# SCH_Syntheseproject_Proof_of_concept_mot.net
KiCad netlist of a schematic drawn in EasyEDA
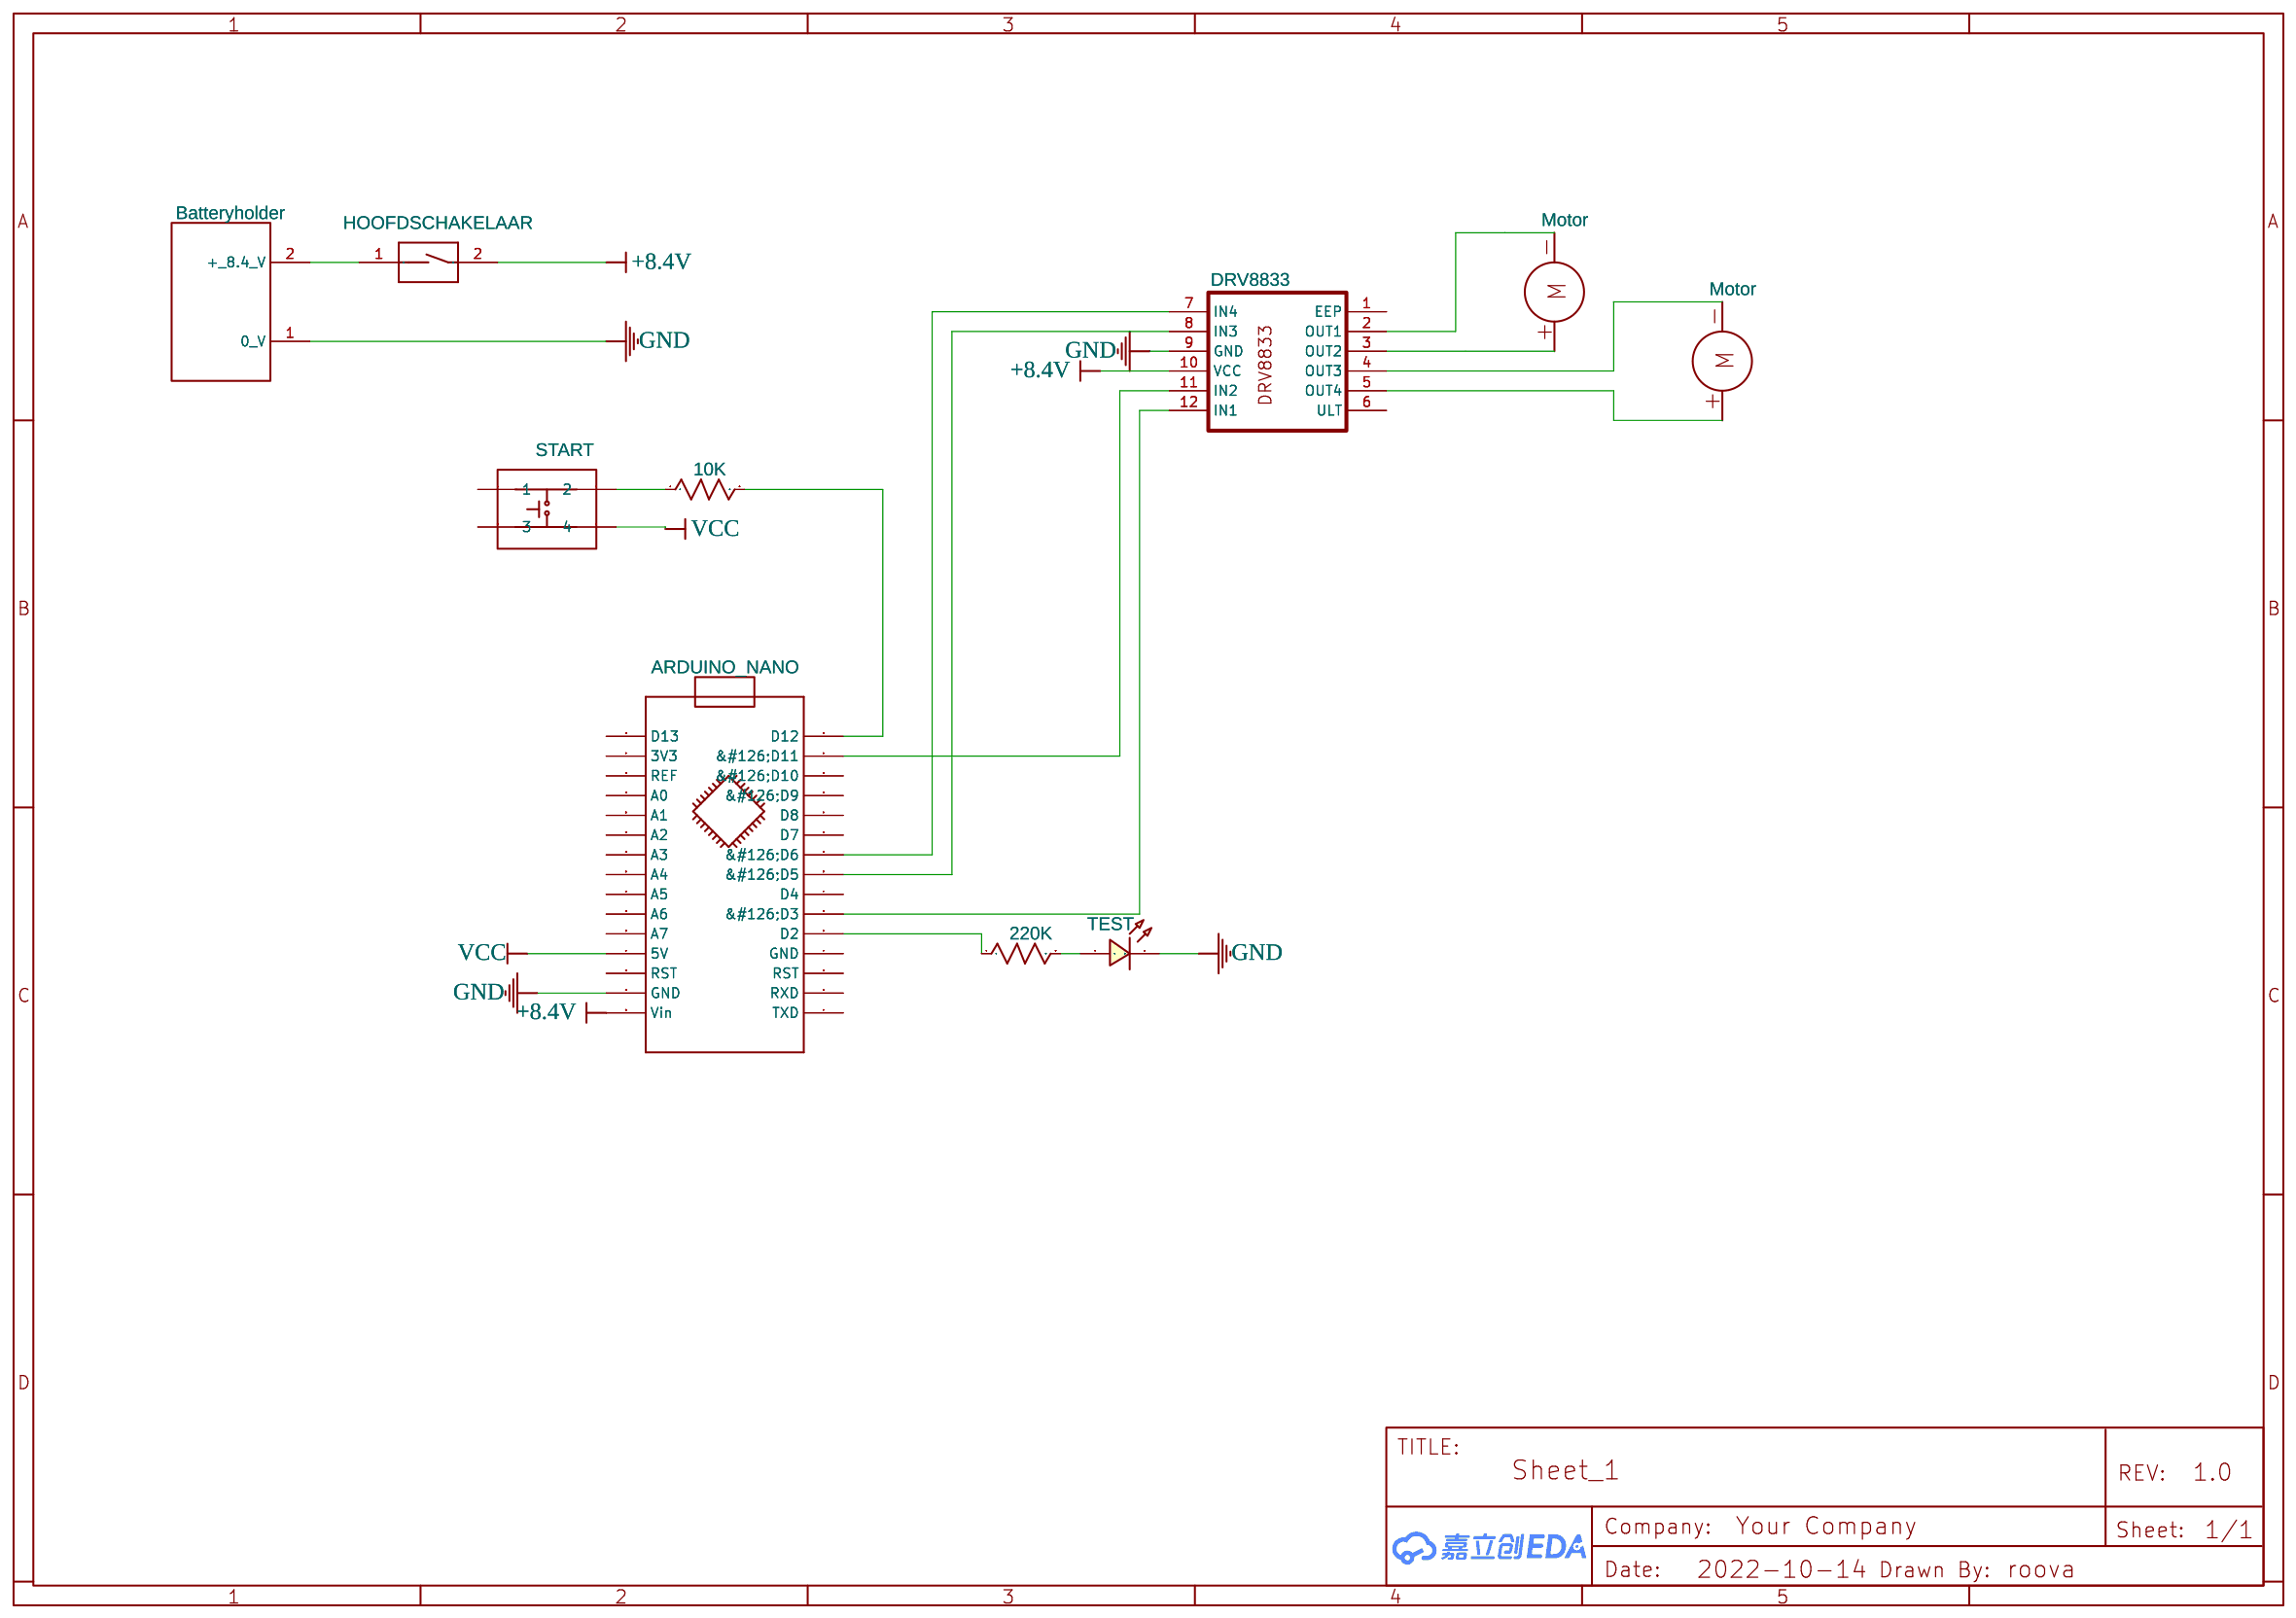
[diagram p0: schematic sheet]

(export (version "E")
  (design (tool "Eeschema 10.0.6"))
  (components
    (comp (ref "10K") (value "1k") (libsource (lib "") (part "R_0603_US_1")))
    (comp (ref "220K") (value "1k") (libsource (lib "") (part "R_0603_US")))
    (comp (ref "ARDUINO_NANO")
      (value "ARDUINO-NANO_V3")
      (fields (field (name "BOM_Manufacturer Part") "ARDUINO-NANO_AK"))
      (libsource (lib "") (part "ARDUINO-NANO_V3"))
    )
    (comp (ref "HOOFDSCHAKELAAR")
      (value "DIP1")
      (fields
        (field (name "BOM_Manufacturer Part") "A6TN-1101")
        (field (name "BOM_Supplier Part") "Z12167-ND")
      )
      (libsource (lib "") (part "DIP1"))
    )
    (comp (ref "M2") (value "Motor") (libsource (lib "") (part "Motor")))
    (comp (ref "M3") (value "Motor") (libsource (lib "") (part "Motor")))
    (comp (ref "START")
      (value "PUSHBUTTON 6X6X4.5 4 PINS COPY")
      (fields (field (name "BOM_Manufacturer Part") "sparkfun"))
      (libsource (lib "") (part "PUSHBUTTON 6X6X4.5 4 PINS COPY"))
    )
    (comp (ref "TEST")
      (value "LED-0603_R")
      (fields
        (field (name "BOM_Manufacturer Part") "19-217/R6C-AL1M2VY/3T")
        (field (name "BOM_Supplier Part") "C72044")
      )
      (libsource (lib "") (part "LED-0603_R"))
    )
    (comp (ref "U1") (value "DRV8833") (libsource (lib "") (part "DRV8833 (NO ORIGINAL)")))
    (comp (ref "U4") (value "Batteryholder") (libsource (lib "") (part "Batteryholder")))
  )
  (nets
    (net (code "1") (name "+8.4V") (class "Default")
      (node (ref "ARDUINO_NANO") (pin "30") (pinfunction "Vin_30") (pintype "unspecified"))
      (node (ref "HOOFDSCHAKELAAR") (pin "2") (pinfunction "2_2") (pintype "unspecified"))
      (node (ref "U1") (pin "10") (pinfunction "VCC_10") (pintype "unspecified"))
    )
    (net (code "2") (name "GND") (class "Default")
      (node (ref "ARDUINO_NANO") (pin "29") (pinfunction "GND_29") (pintype "unspecified"))
      (node (ref "TEST") (pin "2") (pinfunction "2_2") (pintype "unspecified"))
      (node (ref "U1") (pin "9") (pinfunction "GND_9") (pintype "unspecified"))
      (node (ref "U4") (pin "1") (pinfunction "0_V_1") (pintype "unspecified"))
    )
    (net (code "3") (name "Net-(10K-Pad1)") (class "Default")
      (node (ref "10K") (pin "1") (pinfunction "1_1") (pintype "unspecified"))
      (node (ref "START") (pin "2") (pinfunction "2_2") (pintype "unspecified"))
    )
    (net (code "4") (name "Net-(220K-Pad2)") (class "Default")
      (node (ref "220K") (pin "2") (pinfunction "2_2") (pintype "unspecified"))
      (node (ref "TEST") (pin "1") (pinfunction "1_1") (pintype "unspecified"))
    )
    (net (code "5") (name "Net-(ARDUINO_NANO-&#126;D3)") (class "Default")
      (node (ref "ARDUINO_NANO") (pin "6") (pinfunction "&#126;D3_6") (pintype "unspecified"))
      (node (ref "U1") (pin "12") (pinfunction "IN1_12") (pintype "unspecified"))
    )
    (net (code "6") (name "Net-(ARDUINO_NANO-&#126;D5)") (class "Default")
      (node (ref "ARDUINO_NANO") (pin "8") (pinfunction "&#126;D5_8") (pintype "unspecified"))
      (node (ref "U1") (pin "8") (pinfunction "IN3_8") (pintype "unspecified"))
    )
    (net (code "7") (name "Net-(ARDUINO_NANO-&#126;D6)") (class "Default")
      (node (ref "ARDUINO_NANO") (pin "9") (pinfunction "&#126;D6_9") (pintype "unspecified"))
      (node (ref "U1") (pin "7") (pinfunction "IN4_7") (pintype "unspecified"))
    )
    (net (code "8") (name "Net-(ARDUINO_NANO-&#126;D11)") (class "Default")
      (node (ref "ARDUINO_NANO") (pin "14") (pinfunction "&#126;D11_14") (pintype "unspecified"))
      (node (ref "U1") (pin "11") (pinfunction "IN2_11") (pintype "unspecified"))
    )
    (net (code "9") (name "Net-(ARDUINO_NANO-D2)") (class "Default")
      (node (ref "220K") (pin "1") (pinfunction "1_1") (pintype "unspecified"))
      (node (ref "ARDUINO_NANO") (pin "5") (pinfunction "D2_5") (pintype "unspecified"))
    )
    (net (code "10") (name "Net-(ARDUINO_NANO-D12)") (class "Default")
      (node (ref "10K") (pin "2") (pinfunction "2_2") (pintype "unspecified"))
      (node (ref "ARDUINO_NANO") (pin "15") (pinfunction "D12_15") (pintype "unspecified"))
    )
    (net (code "11") (name "Net-(U4-+_8.4_V)") (class "Default")
      (node (ref "HOOFDSCHAKELAAR") (pin "1") (pinfunction "1_1") (pintype "unspecified"))
      (node (ref "U4") (pin "2") (pinfunction "+_8.4_V_2") (pintype "unspecified"))
    )
    (net (code "12") (name "VCC") (class "Default")
      (node (ref "ARDUINO_NANO") (pin "27") (pinfunction "5V_27") (pintype "unspecified"))
      (node (ref "START") (pin "4") (pinfunction "4_4") (pintype "unspecified"))
    )
    (net (code "13") (name "unconnected-(ARDUINO_NANO-&#126;D9-Pad12)") (class "Default")
      (node (ref "ARDUINO_NANO") (pin "12") (pinfunction "&#126;D9_12") (pintype "unspecified"))
    )
    (net (code "14") (name "unconnected-(ARDUINO_NANO-&#126;D10-Pad13)") (class "Default")
      (node (ref "ARDUINO_NANO") (pin "13") (pinfunction "&#126;D10_13") (pintype "unspecified"))
    )
    (net (code "15") (name "unconnected-(ARDUINO_NANO-3V3-Pad17)") (class "Default")
      (node (ref "ARDUINO_NANO") (pin "17") (pinfunction "3V3_17") (pintype "unspecified"))
    )
    (net (code "16") (name "unconnected-(ARDUINO_NANO-A0-Pad19)") (class "Default")
      (node (ref "ARDUINO_NANO") (pin "19") (pinfunction "A0_19") (pintype "unspecified"))
    )
    (net (code "17") (name "unconnected-(ARDUINO_NANO-A1-Pad20)") (class "Default")
      (node (ref "ARDUINO_NANO") (pin "20") (pinfunction "A1_20") (pintype "unspecified"))
    )
    (net (code "18") (name "unconnected-(ARDUINO_NANO-A2-Pad21)") (class "Default")
      (node (ref "ARDUINO_NANO") (pin "21") (pinfunction "A2_21") (pintype "unspecified"))
    )
    (net (code "19") (name "unconnected-(ARDUINO_NANO-A3-Pad22)") (class "Default")
      (node (ref "ARDUINO_NANO") (pin "22") (pinfunction "A3_22") (pintype "unspecified"))
    )
    (net (code "20") (name "unconnected-(ARDUINO_NANO-A4-Pad23)") (class "Default")
      (node (ref "ARDUINO_NANO") (pin "23") (pinfunction "A4_23") (pintype "unspecified"))
    )
    (net (code "21") (name "unconnected-(ARDUINO_NANO-A5-Pad24)") (class "Default")
      (node (ref "ARDUINO_NANO") (pin "24") (pinfunction "A5_24") (pintype "unspecified"))
    )
    (net (code "22") (name "unconnected-(ARDUINO_NANO-A6-Pad25)") (class "Default")
      (node (ref "ARDUINO_NANO") (pin "25") (pinfunction "A6_25") (pintype "unspecified"))
    )
    (net (code "23") (name "unconnected-(ARDUINO_NANO-A7-Pad26)") (class "Default")
      (node (ref "ARDUINO_NANO") (pin "26") (pinfunction "A7_26") (pintype "unspecified"))
    )
    (net (code "24") (name "unconnected-(ARDUINO_NANO-D4-Pad7)") (class "Default")
      (node (ref "ARDUINO_NANO") (pin "7") (pinfunction "D4_7") (pintype "unspecified"))
    )
    (net (code "25") (name "unconnected-(ARDUINO_NANO-D7-Pad10)") (class "Default")
      (node (ref "ARDUINO_NANO") (pin "10") (pinfunction "D7_10") (pintype "unspecified"))
    )
    (net (code "26") (name "unconnected-(ARDUINO_NANO-D8-Pad11)") (class "Default")
      (node (ref "ARDUINO_NANO") (pin "11") (pinfunction "D8_11") (pintype "unspecified"))
    )
    (net (code "27") (name "unconnected-(ARDUINO_NANO-D13-Pad16)") (class "Default")
      (node (ref "ARDUINO_NANO") (pin "16") (pinfunction "D13_16") (pintype "unspecified"))
    )
    (net (code "28") (name "unconnected-(ARDUINO_NANO-GND-Pad4)") (class "Default")
      (node (ref "ARDUINO_NANO") (pin "4") (pinfunction "GND_4") (pintype "unspecified"))
    )
    (net (code "29") (name "unconnected-(ARDUINO_NANO-REF-Pad18)") (class "Default")
      (node (ref "ARDUINO_NANO") (pin "18") (pinfunction "REF_18") (pintype "unspecified"))
    )
    (net (code "30") (name "unconnected-(ARDUINO_NANO-RST-Pad3)") (class "Default")
      (node (ref "ARDUINO_NANO") (pin "3") (pinfunction "RST_3") (pintype "unspecified"))
    )
    (net (code "31") (name "unconnected-(ARDUINO_NANO-RST-Pad28)") (class "Default")
      (node (ref "ARDUINO_NANO") (pin "28") (pinfunction "RST_28") (pintype "unspecified"))
    )
    (net (code "32") (name "unconnected-(ARDUINO_NANO-RXD-Pad2)") (class "Default")
      (node (ref "ARDUINO_NANO") (pin "2") (pinfunction "RXD_2") (pintype "unspecified"))
    )
    (net (code "33") (name "unconnected-(ARDUINO_NANO-TXD-Pad1)") (class "Default")
      (node (ref "ARDUINO_NANO") (pin "1") (pinfunction "TXD_1") (pintype "unspecified"))
    )
    (net (code "34") (name "unconnected-(START-Pad1)") (class "Default")
      (node (ref "START") (pin "1") (pinfunction "1_1") (pintype "unspecified"))
    )
    (net (code "35") (name "unconnected-(START-Pad3)") (class "Default")
      (node (ref "START") (pin "3") (pinfunction "3_3") (pintype "unspecified"))
    )
    (net (code "36") (name "unconnected-(U1-EEP-Pad1)") (class "Default")
      (node (ref "U1") (pin "1") (pinfunction "EEP_1") (pintype "unspecified"))
    )
    (net (code "37") (name "unconnected-(U1-OUT1-Pad2)") (class "Default")
      (node (ref "U1") (pin "2") (pinfunction "OUT1_2") (pintype "unspecified"))
    )
    (net (code "38") (name "unconnected-(U1-OUT2-Pad3)") (class "Default")
      (node (ref "U1") (pin "3") (pinfunction "OUT2_3") (pintype "unspecified"))
    )
    (net (code "39") (name "unconnected-(U1-OUT3-Pad4)") (class "Default")
      (node (ref "U1") (pin "4") (pinfunction "OUT3_4") (pintype "unspecified"))
    )
    (net (code "40") (name "unconnected-(U1-OUT4-Pad5)") (class "Default")
      (node (ref "U1") (pin "5") (pinfunction "OUT4_5") (pintype "unspecified"))
    )
    (net (code "41") (name "unconnected-(U1-ULT-Pad6)") (class "Default")
      (node (ref "U1") (pin "6") (pinfunction "ULT_6") (pintype "unspecified"))
    )
  )
)
